# BLOCKS.net
KiCad netlist of a schematic drawn in EAGLE
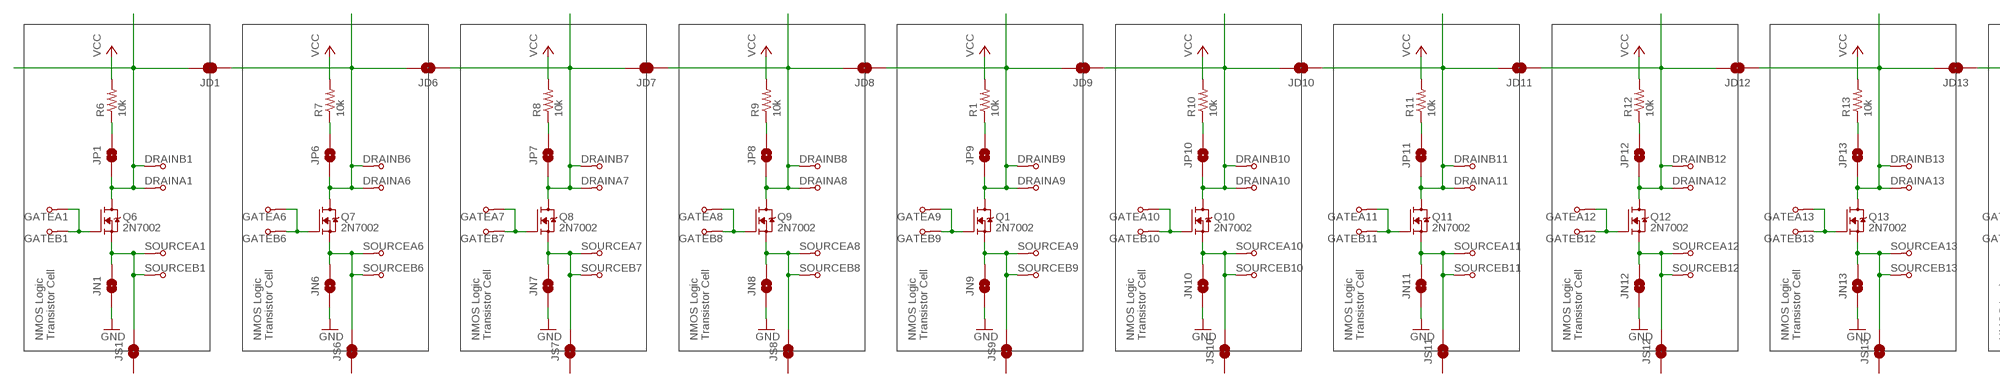
[diagram p0: schematic, sheet 1, part 1 of 2]
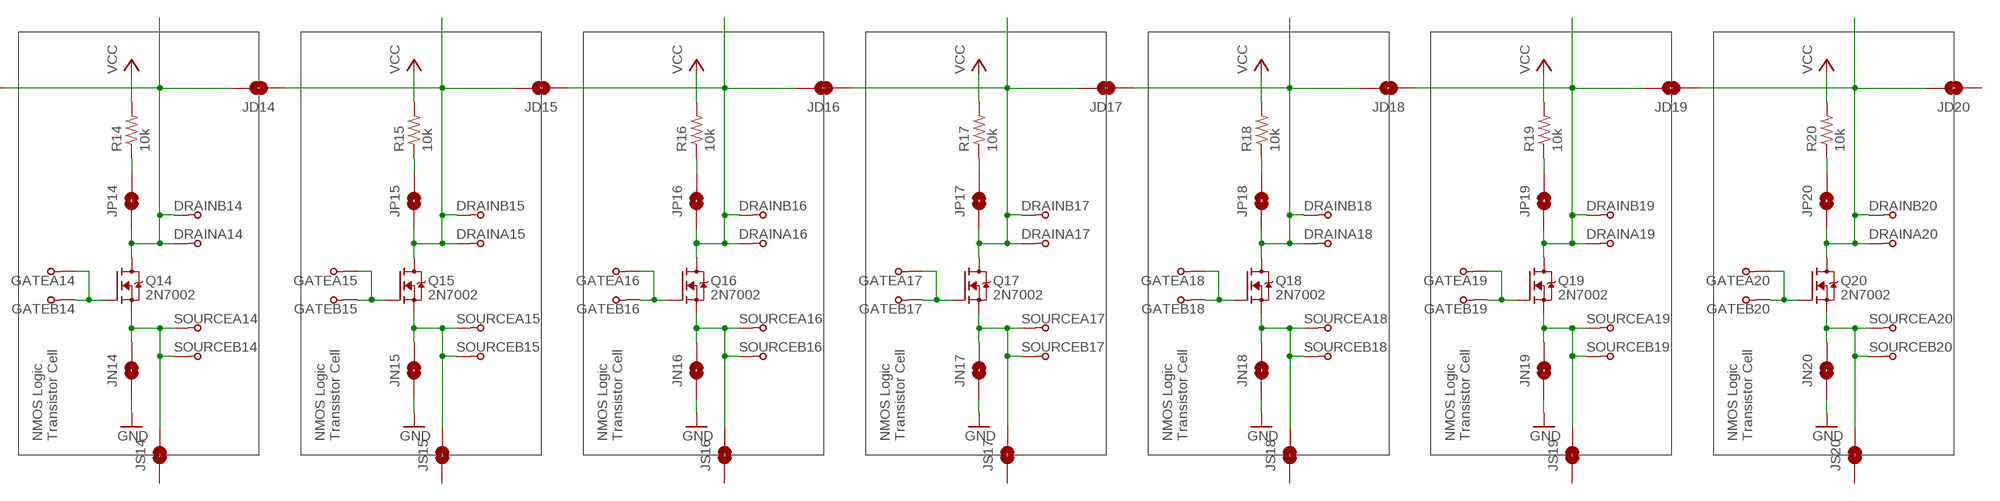
[diagram p1: schematic, sheet 1, part 2 of 2]

(export (version "E")
  (design (tool "Eeschema 10.0.6"))
  (components
    (comp (ref "DRAINA1")
      (value "TPTHT")
      (footprint "eagle-import:PROTOPAD-THT-PAD")
      (libsource (lib "eagle-import") (part "TPTHT"))
    )
    (comp (ref "DRAINA6")
      (value "TPTHT")
      (footprint "eagle-import:PROTOPAD-THT-PAD")
      (libsource (lib "eagle-import") (part "TPTHT"))
    )
    (comp (ref "DRAINA7")
      (value "TPTHT")
      (footprint "eagle-import:PROTOPAD-THT-PAD")
      (libsource (lib "eagle-import") (part "TPTHT"))
    )
    (comp (ref "DRAINA8")
      (value "TPTHT")
      (footprint "eagle-import:PROTOPAD-THT-PAD")
      (libsource (lib "eagle-import") (part "TPTHT"))
    )
    (comp (ref "DRAINA9")
      (value "TPTHT")
      (footprint "eagle-import:PROTOPAD-THT-PAD")
      (libsource (lib "eagle-import") (part "TPTHT"))
    )
    (comp (ref "DRAINA10")
      (value "TPTHT")
      (footprint "eagle-import:PROTOPAD-THT-PAD")
      (libsource (lib "eagle-import") (part "TPTHT"))
    )
    (comp (ref "DRAINA11")
      (value "TPTHT")
      (footprint "eagle-import:PROTOPAD-THT-PAD")
      (libsource (lib "eagle-import") (part "TPTHT"))
    )
    (comp (ref "DRAINA12")
      (value "TPTHT")
      (footprint "eagle-import:PROTOPAD-THT-PAD")
      (libsource (lib "eagle-import") (part "TPTHT"))
    )
    (comp (ref "DRAINA13")
      (value "TPTHT")
      (footprint "eagle-import:PROTOPAD-THT-PAD")
      (libsource (lib "eagle-import") (part "TPTHT"))
    )
    (comp (ref "DRAINA14")
      (value "TPTHT")
      (footprint "eagle-import:PROTOPAD-THT-PAD")
      (libsource (lib "eagle-import") (part "TPTHT"))
    )
    (comp (ref "DRAINA15")
      (value "TPTHT")
      (footprint "eagle-import:PROTOPAD-THT-PAD")
      (libsource (lib "eagle-import") (part "TPTHT"))
    )
    (comp (ref "DRAINA16")
      (value "TPTHT")
      (footprint "eagle-import:PROTOPAD-THT-PAD")
      (libsource (lib "eagle-import") (part "TPTHT"))
    )
    (comp (ref "DRAINA17")
      (value "TPTHT")
      (footprint "eagle-import:PROTOPAD-THT-PAD")
      (libsource (lib "eagle-import") (part "TPTHT"))
    )
    (comp (ref "DRAINA18")
      (value "TPTHT")
      (footprint "eagle-import:PROTOPAD-THT-PAD")
      (libsource (lib "eagle-import") (part "TPTHT"))
    )
    (comp (ref "DRAINA19")
      (value "TPTHT")
      (footprint "eagle-import:PROTOPAD-THT-PAD")
      (libsource (lib "eagle-import") (part "TPTHT"))
    )
    (comp (ref "DRAINA20")
      (value "TPTHT")
      (footprint "eagle-import:PROTOPAD-THT-PAD")
      (libsource (lib "eagle-import") (part "TPTHT"))
    )
    (comp (ref "DRAINB1")
      (value "TPTHT")
      (footprint "eagle-import:PROTOPAD-THT-PAD")
      (libsource (lib "eagle-import") (part "TPTHT"))
    )
    (comp (ref "DRAINB6")
      (value "TPTHT")
      (footprint "eagle-import:PROTOPAD-THT-PAD")
      (libsource (lib "eagle-import") (part "TPTHT"))
    )
    (comp (ref "DRAINB7")
      (value "TPTHT")
      (footprint "eagle-import:PROTOPAD-THT-PAD")
      (libsource (lib "eagle-import") (part "TPTHT"))
    )
    (comp (ref "DRAINB8")
      (value "TPTHT")
      (footprint "eagle-import:PROTOPAD-THT-PAD")
      (libsource (lib "eagle-import") (part "TPTHT"))
    )
    (comp (ref "DRAINB9")
      (value "TPTHT")
      (footprint "eagle-import:PROTOPAD-THT-PAD")
      (libsource (lib "eagle-import") (part "TPTHT"))
    )
    (comp (ref "DRAINB10")
      (value "TPTHT")
      (footprint "eagle-import:PROTOPAD-THT-PAD")
      (libsource (lib "eagle-import") (part "TPTHT"))
    )
    (comp (ref "DRAINB11")
      (value "TPTHT")
      (footprint "eagle-import:PROTOPAD-THT-PAD")
      (libsource (lib "eagle-import") (part "TPTHT"))
    )
    (comp (ref "DRAINB12")
      (value "TPTHT")
      (footprint "eagle-import:PROTOPAD-THT-PAD")
      (libsource (lib "eagle-import") (part "TPTHT"))
    )
    (comp (ref "DRAINB13")
      (value "TPTHT")
      (footprint "eagle-import:PROTOPAD-THT-PAD")
      (libsource (lib "eagle-import") (part "TPTHT"))
    )
    (comp (ref "DRAINB14")
      (value "TPTHT")
      (footprint "eagle-import:PROTOPAD-THT-PAD")
      (libsource (lib "eagle-import") (part "TPTHT"))
    )
    (comp (ref "DRAINB15")
      (value "TPTHT")
      (footprint "eagle-import:PROTOPAD-THT-PAD")
      (libsource (lib "eagle-import") (part "TPTHT"))
    )
    (comp (ref "DRAINB16")
      (value "TPTHT")
      (footprint "eagle-import:PROTOPAD-THT-PAD")
      (libsource (lib "eagle-import") (part "TPTHT"))
    )
    (comp (ref "DRAINB17")
      (value "TPTHT")
      (footprint "eagle-import:PROTOPAD-THT-PAD")
      (libsource (lib "eagle-import") (part "TPTHT"))
    )
    (comp (ref "DRAINB18")
      (value "TPTHT")
      (footprint "eagle-import:PROTOPAD-THT-PAD")
      (libsource (lib "eagle-import") (part "TPTHT"))
    )
    (comp (ref "DRAINB19")
      (value "TPTHT")
      (footprint "eagle-import:PROTOPAD-THT-PAD")
      (libsource (lib "eagle-import") (part "TPTHT"))
    )
    (comp (ref "DRAINB20")
      (value "TPTHT")
      (footprint "eagle-import:PROTOPAD-THT-PAD")
      (libsource (lib "eagle-import") (part "TPTHT"))
    )
    (comp (ref "GATEA1")
      (value "TPTHT")
      (footprint "eagle-import:PROTOPAD-THT-PAD")
      (libsource (lib "eagle-import") (part "TPTHT"))
    )
    (comp (ref "GATEA6")
      (value "TPTHT")
      (footprint "eagle-import:PROTOPAD-THT-PAD")
      (libsource (lib "eagle-import") (part "TPTHT"))
    )
    (comp (ref "GATEA7")
      (value "TPTHT")
      (footprint "eagle-import:PROTOPAD-THT-PAD")
      (libsource (lib "eagle-import") (part "TPTHT"))
    )
    (comp (ref "GATEA8")
      (value "TPTHT")
      (footprint "eagle-import:PROTOPAD-THT-PAD")
      (libsource (lib "eagle-import") (part "TPTHT"))
    )
    (comp (ref "GATEA9")
      (value "TPTHT")
      (footprint "eagle-import:PROTOPAD-THT-PAD")
      (libsource (lib "eagle-import") (part "TPTHT"))
    )
    (comp (ref "GATEA10")
      (value "TPTHT")
      (footprint "eagle-import:PROTOPAD-THT-PAD")
      (libsource (lib "eagle-import") (part "TPTHT"))
    )
    (comp (ref "GATEA11")
      (value "TPTHT")
      (footprint "eagle-import:PROTOPAD-THT-PAD")
      (libsource (lib "eagle-import") (part "TPTHT"))
    )
    (comp (ref "GATEA12")
      (value "TPTHT")
      (footprint "eagle-import:PROTOPAD-THT-PAD")
      (libsource (lib "eagle-import") (part "TPTHT"))
    )
    (comp (ref "GATEA13")
      (value "TPTHT")
      (footprint "eagle-import:PROTOPAD-THT-PAD")
      (libsource (lib "eagle-import") (part "TPTHT"))
    )
    (comp (ref "GATEA14")
      (value "TPTHT")
      (footprint "eagle-import:PROTOPAD-THT-PAD")
      (libsource (lib "eagle-import") (part "TPTHT"))
    )
    (comp (ref "GATEA15")
      (value "TPTHT")
      (footprint "eagle-import:PROTOPAD-THT-PAD")
      (libsource (lib "eagle-import") (part "TPTHT"))
    )
    (comp (ref "GATEA16")
      (value "TPTHT")
      (footprint "eagle-import:PROTOPAD-THT-PAD")
      (libsource (lib "eagle-import") (part "TPTHT"))
    )
    (comp (ref "GATEA17")
      (value "TPTHT")
      (footprint "eagle-import:PROTOPAD-THT-PAD")
      (libsource (lib "eagle-import") (part "TPTHT"))
    )
    (comp (ref "GATEA18")
      (value "TPTHT")
      (footprint "eagle-import:PROTOPAD-THT-PAD")
      (libsource (lib "eagle-import") (part "TPTHT"))
    )
    (comp (ref "GATEA19")
      (value "TPTHT")
      (footprint "eagle-import:PROTOPAD-THT-PAD")
      (libsource (lib "eagle-import") (part "TPTHT"))
    )
    (comp (ref "GATEA20")
      (value "TPTHT")
      (footprint "eagle-import:PROTOPAD-THT-PAD")
      (libsource (lib "eagle-import") (part "TPTHT"))
    )
    (comp (ref "GATEB1")
      (value "TPTHT")
      (footprint "eagle-import:PROTOPAD-THT-PAD")
      (libsource (lib "eagle-import") (part "TPTHT"))
    )
    (comp (ref "GATEB6")
      (value "TPTHT")
      (footprint "eagle-import:PROTOPAD-THT-PAD")
      (libsource (lib "eagle-import") (part "TPTHT"))
    )
    (comp (ref "GATEB7")
      (value "TPTHT")
      (footprint "eagle-import:PROTOPAD-THT-PAD")
      (libsource (lib "eagle-import") (part "TPTHT"))
    )
    (comp (ref "GATEB8")
      (value "TPTHT")
      (footprint "eagle-import:PROTOPAD-THT-PAD")
      (libsource (lib "eagle-import") (part "TPTHT"))
    )
    (comp (ref "GATEB9")
      (value "TPTHT")
      (footprint "eagle-import:PROTOPAD-THT-PAD")
      (libsource (lib "eagle-import") (part "TPTHT"))
    )
    (comp (ref "GATEB10")
      (value "TPTHT")
      (footprint "eagle-import:PROTOPAD-THT-PAD")
      (libsource (lib "eagle-import") (part "TPTHT"))
    )
    (comp (ref "GATEB11")
      (value "TPTHT")
      (footprint "eagle-import:PROTOPAD-THT-PAD")
      (libsource (lib "eagle-import") (part "TPTHT"))
    )
    (comp (ref "GATEB12")
      (value "TPTHT")
      (footprint "eagle-import:PROTOPAD-THT-PAD")
      (libsource (lib "eagle-import") (part "TPTHT"))
    )
    (comp (ref "GATEB13")
      (value "TPTHT")
      (footprint "eagle-import:PROTOPAD-THT-PAD")
      (libsource (lib "eagle-import") (part "TPTHT"))
    )
    (comp (ref "GATEB14")
      (value "TPTHT")
      (footprint "eagle-import:PROTOPAD-THT-PAD")
      (libsource (lib "eagle-import") (part "TPTHT"))
    )
    (comp (ref "GATEB15")
      (value "TPTHT")
      (footprint "eagle-import:PROTOPAD-THT-PAD")
      (libsource (lib "eagle-import") (part "TPTHT"))
    )
    (comp (ref "GATEB16")
      (value "TPTHT")
      (footprint "eagle-import:PROTOPAD-THT-PAD")
      (libsource (lib "eagle-import") (part "TPTHT"))
    )
    (comp (ref "GATEB17")
      (value "TPTHT")
      (footprint "eagle-import:PROTOPAD-THT-PAD")
      (libsource (lib "eagle-import") (part "TPTHT"))
    )
    (comp (ref "GATEB18")
      (value "TPTHT")
      (footprint "eagle-import:PROTOPAD-THT-PAD")
      (libsource (lib "eagle-import") (part "TPTHT"))
    )
    (comp (ref "GATEB19")
      (value "TPTHT")
      (footprint "eagle-import:PROTOPAD-THT-PAD")
      (libsource (lib "eagle-import") (part "TPTHT"))
    )
    (comp (ref "GATEB20")
      (value "TPTHT")
      (footprint "eagle-import:PROTOPAD-THT-PAD")
      (libsource (lib "eagle-import") (part "TPTHT"))
    )
    (comp (ref "JD1")
      (value "SJ_NO_THIN")
      (footprint "eagle-import:SJ_2S-NO-THIN")
      (libsource (lib "eagle-import") (part "SJ_NO_THIN"))
    )
    (comp (ref "JD6")
      (value "SJ_NO_THIN")
      (footprint "eagle-import:SJ_2S-NO-THIN")
      (libsource (lib "eagle-import") (part "SJ_NO_THIN"))
    )
    (comp (ref "JD7")
      (value "SJ_NO_THIN")
      (footprint "eagle-import:SJ_2S-NO-THIN")
      (libsource (lib "eagle-import") (part "SJ_NO_THIN"))
    )
    (comp (ref "JD8")
      (value "SJ_NO_THIN")
      (footprint "eagle-import:SJ_2S-NO-THIN")
      (libsource (lib "eagle-import") (part "SJ_NO_THIN"))
    )
    (comp (ref "JD9")
      (value "SJ_NO_THIN")
      (footprint "eagle-import:SJ_2S-NO-THIN")
      (libsource (lib "eagle-import") (part "SJ_NO_THIN"))
    )
    (comp (ref "JD10")
      (value "SJ_NO_THIN")
      (footprint "eagle-import:SJ_2S-NO-THIN")
      (libsource (lib "eagle-import") (part "SJ_NO_THIN"))
    )
    (comp (ref "JD11")
      (value "SJ_NO_THIN")
      (footprint "eagle-import:SJ_2S-NO-THIN")
      (libsource (lib "eagle-import") (part "SJ_NO_THIN"))
    )
    (comp (ref "JD12")
      (value "SJ_NO_THIN")
      (footprint "eagle-import:SJ_2S-NO-THIN")
      (libsource (lib "eagle-import") (part "SJ_NO_THIN"))
    )
    (comp (ref "JD13")
      (value "SJ_NO_THIN")
      (footprint "eagle-import:SJ_2S-NO-THIN")
      (libsource (lib "eagle-import") (part "SJ_NO_THIN"))
    )
    (comp (ref "JD14")
      (value "SJ_NO_THIN")
      (footprint "eagle-import:SJ_2S-NO-THIN")
      (libsource (lib "eagle-import") (part "SJ_NO_THIN"))
    )
    (comp (ref "JD15")
      (value "SJ_NO_THIN")
      (footprint "eagle-import:SJ_2S-NO-THIN")
      (libsource (lib "eagle-import") (part "SJ_NO_THIN"))
    )
    (comp (ref "JD16")
      (value "SJ_NO_THIN")
      (footprint "eagle-import:SJ_2S-NO-THIN")
      (libsource (lib "eagle-import") (part "SJ_NO_THIN"))
    )
    (comp (ref "JD17")
      (value "SJ_NO_THIN")
      (footprint "eagle-import:SJ_2S-NO-THIN")
      (libsource (lib "eagle-import") (part "SJ_NO_THIN"))
    )
    (comp (ref "JD18")
      (value "SJ_NO_THIN")
      (footprint "eagle-import:SJ_2S-NO-THIN")
      (libsource (lib "eagle-import") (part "SJ_NO_THIN"))
    )
    (comp (ref "JD19")
      (value "SJ_NO_THIN")
      (footprint "eagle-import:SJ_2S-NO-THIN")
      (libsource (lib "eagle-import") (part "SJ_NO_THIN"))
    )
    (comp (ref "JD20")
      (value "SJ_NO_THIN")
      (footprint "eagle-import:SJ_2S-NO-THIN")
      (libsource (lib "eagle-import") (part "SJ_NO_THIN"))
    )
    (comp (ref "JN1")
      (value "SJ_NO_THIN")
      (footprint "eagle-import:SJ_2S-NO-THIN")
      (libsource (lib "eagle-import") (part "SJ_NO_THIN"))
    )
    (comp (ref "JN6")
      (value "SJ_NO_THIN")
      (footprint "eagle-import:SJ_2S-NO-THIN")
      (libsource (lib "eagle-import") (part "SJ_NO_THIN"))
    )
    (comp (ref "JN7")
      (value "SJ_NO_THIN")
      (footprint "eagle-import:SJ_2S-NO-THIN")
      (libsource (lib "eagle-import") (part "SJ_NO_THIN"))
    )
    (comp (ref "JN8")
      (value "SJ_NO_THIN")
      (footprint "eagle-import:SJ_2S-NO-THIN")
      (libsource (lib "eagle-import") (part "SJ_NO_THIN"))
    )
    (comp (ref "JN9")
      (value "SJ_NO_THIN")
      (footprint "eagle-import:SJ_2S-NO-THIN")
      (libsource (lib "eagle-import") (part "SJ_NO_THIN"))
    )
    (comp (ref "JN10")
      (value "SJ_NO_THIN")
      (footprint "eagle-import:SJ_2S-NO-THIN")
      (libsource (lib "eagle-import") (part "SJ_NO_THIN"))
    )
    (comp (ref "JN11")
      (value "SJ_NO_THIN")
      (footprint "eagle-import:SJ_2S-NO-THIN")
      (libsource (lib "eagle-import") (part "SJ_NO_THIN"))
    )
    (comp (ref "JN12")
      (value "SJ_NO_THIN")
      (footprint "eagle-import:SJ_2S-NO-THIN")
      (libsource (lib "eagle-import") (part "SJ_NO_THIN"))
    )
    (comp (ref "JN13")
      (value "SJ_NO_THIN")
      (footprint "eagle-import:SJ_2S-NO-THIN")
      (libsource (lib "eagle-import") (part "SJ_NO_THIN"))
    )
    (comp (ref "JN14")
      (value "SJ_NO_THIN")
      (footprint "eagle-import:SJ_2S-NO-THIN")
      (libsource (lib "eagle-import") (part "SJ_NO_THIN"))
    )
    (comp (ref "JN15")
      (value "SJ_NO_THIN")
      (footprint "eagle-import:SJ_2S-NO-THIN")
      (libsource (lib "eagle-import") (part "SJ_NO_THIN"))
    )
    (comp (ref "JN16")
      (value "SJ_NO_THIN")
      (footprint "eagle-import:SJ_2S-NO-THIN")
      (libsource (lib "eagle-import") (part "SJ_NO_THIN"))
    )
    (comp (ref "JN17")
      (value "SJ_NO_THIN")
      (footprint "eagle-import:SJ_2S-NO-THIN")
      (libsource (lib "eagle-import") (part "SJ_NO_THIN"))
    )
    (comp (ref "JN18")
      (value "SJ_NO_THIN")
      (footprint "eagle-import:SJ_2S-NO-THIN")
      (libsource (lib "eagle-import") (part "SJ_NO_THIN"))
    )
    (comp (ref "JN19")
      (value "SJ_NO_THIN")
      (footprint "eagle-import:SJ_2S-NO-THIN")
      (libsource (lib "eagle-import") (part "SJ_NO_THIN"))
    )
    (comp (ref "JN20")
      (value "SJ_NO_THIN")
      (footprint "eagle-import:SJ_2S-NO-THIN")
      (libsource (lib "eagle-import") (part "SJ_NO_THIN"))
    )
    (comp (ref "JP1")
      (value "SJ_NO_THIN")
      (footprint "eagle-import:SJ_2S-NO-THIN")
      (libsource (lib "eagle-import") (part "SJ_NO_THIN"))
    )
    (comp (ref "JP6")
      (value "SJ_NO_THIN")
      (footprint "eagle-import:SJ_2S-NO-THIN")
      (libsource (lib "eagle-import") (part "SJ_NO_THIN"))
    )
    (comp (ref "JP7")
      (value "SJ_NO_THIN")
      (footprint "eagle-import:SJ_2S-NO-THIN")
      (libsource (lib "eagle-import") (part "SJ_NO_THIN"))
    )
    (comp (ref "JP8")
      (value "SJ_NO_THIN")
      (footprint "eagle-import:SJ_2S-NO-THIN")
      (libsource (lib "eagle-import") (part "SJ_NO_THIN"))
    )
    (comp (ref "JP9")
      (value "SJ_NO_THIN")
      (footprint "eagle-import:SJ_2S-NO-THIN")
      (libsource (lib "eagle-import") (part "SJ_NO_THIN"))
    )
    (comp (ref "JP10")
      (value "SJ_NO_THIN")
      (footprint "eagle-import:SJ_2S-NO-THIN")
      (libsource (lib "eagle-import") (part "SJ_NO_THIN"))
    )
    (comp (ref "JP11")
      (value "SJ_NO_THIN")
      (footprint "eagle-import:SJ_2S-NO-THIN")
      (libsource (lib "eagle-import") (part "SJ_NO_THIN"))
    )
    (comp (ref "JP12")
      (value "SJ_NO_THIN")
      (footprint "eagle-import:SJ_2S-NO-THIN")
      (libsource (lib "eagle-import") (part "SJ_NO_THIN"))
    )
    (comp (ref "JP13")
      (value "SJ_NO_THIN")
      (footprint "eagle-import:SJ_2S-NO-THIN")
      (libsource (lib "eagle-import") (part "SJ_NO_THIN"))
    )
    (comp (ref "JP14")
      (value "SJ_NO_THIN")
      (footprint "eagle-import:SJ_2S-NO-THIN")
      (libsource (lib "eagle-import") (part "SJ_NO_THIN"))
    )
    (comp (ref "JP15")
      (value "SJ_NO_THIN")
      (footprint "eagle-import:SJ_2S-NO-THIN")
      (libsource (lib "eagle-import") (part "SJ_NO_THIN"))
    )
    (comp (ref "JP16")
      (value "SJ_NO_THIN")
      (footprint "eagle-import:SJ_2S-NO-THIN")
      (libsource (lib "eagle-import") (part "SJ_NO_THIN"))
    )
    (comp (ref "JP17")
      (value "SJ_NO_THIN")
      (footprint "eagle-import:SJ_2S-NO-THIN")
      (libsource (lib "eagle-import") (part "SJ_NO_THIN"))
    )
    (comp (ref "JP18")
      (value "SJ_NO_THIN")
      (footprint "eagle-import:SJ_2S-NO-THIN")
      (libsource (lib "eagle-import") (part "SJ_NO_THIN"))
    )
    (comp (ref "JP19")
      (value "SJ_NO_THIN")
      (footprint "eagle-import:SJ_2S-NO-THIN")
      (libsource (lib "eagle-import") (part "SJ_NO_THIN"))
    )
    (comp (ref "JP20")
      (value "SJ_NO_THIN")
      (footprint "eagle-import:SJ_2S-NO-THIN")
      (libsource (lib "eagle-import") (part "SJ_NO_THIN"))
    )
    (comp (ref "JS1")
      (value "SJ_NO_THIN")
      (footprint "eagle-import:SJ_2S-NO-THIN")
      (libsource (lib "eagle-import") (part "SJ_NO_THIN"))
    )
    (comp (ref "JS6")
      (value "SJ_NO_THIN")
      (footprint "eagle-import:SJ_2S-NO-THIN")
      (libsource (lib "eagle-import") (part "SJ_NO_THIN"))
    )
    (comp (ref "JS7")
      (value "SJ_NO_THIN")
      (footprint "eagle-import:SJ_2S-NO-THIN")
      (libsource (lib "eagle-import") (part "SJ_NO_THIN"))
    )
    (comp (ref "JS8")
      (value "SJ_NO_THIN")
      (footprint "eagle-import:SJ_2S-NO-THIN")
      (libsource (lib "eagle-import") (part "SJ_NO_THIN"))
    )
    (comp (ref "JS9")
      (value "SJ_NO_THIN")
      (footprint "eagle-import:SJ_2S-NO-THIN")
      (libsource (lib "eagle-import") (part "SJ_NO_THIN"))
    )
    (comp (ref "JS10")
      (value "SJ_NO_THIN")
      (footprint "eagle-import:SJ_2S-NO-THIN")
      (libsource (lib "eagle-import") (part "SJ_NO_THIN"))
    )
    (comp (ref "JS11")
      (value "SJ_NO_THIN")
      (footprint "eagle-import:SJ_2S-NO-THIN")
      (libsource (lib "eagle-import") (part "SJ_NO_THIN"))
    )
    (comp (ref "JS12")
      (value "SJ_NO_THIN")
      (footprint "eagle-import:SJ_2S-NO-THIN")
      (libsource (lib "eagle-import") (part "SJ_NO_THIN"))
    )
    (comp (ref "JS13")
      (value "SJ_NO_THIN")
      (footprint "eagle-import:SJ_2S-NO-THIN")
      (libsource (lib "eagle-import") (part "SJ_NO_THIN"))
    )
    (comp (ref "JS14")
      (value "SJ_NO_THIN")
      (footprint "eagle-import:SJ_2S-NO-THIN")
      (libsource (lib "eagle-import") (part "SJ_NO_THIN"))
    )
    (comp (ref "JS15")
      (value "SJ_NO_THIN")
      (footprint "eagle-import:SJ_2S-NO-THIN")
      (libsource (lib "eagle-import") (part "SJ_NO_THIN"))
    )
    (comp (ref "JS16")
      (value "SJ_NO_THIN")
      (footprint "eagle-import:SJ_2S-NO-THIN")
      (libsource (lib "eagle-import") (part "SJ_NO_THIN"))
    )
    (comp (ref "JS17")
      (value "SJ_NO_THIN")
      (footprint "eagle-import:SJ_2S-NO-THIN")
      (libsource (lib "eagle-import") (part "SJ_NO_THIN"))
    )
    (comp (ref "JS18")
      (value "SJ_NO_THIN")
      (footprint "eagle-import:SJ_2S-NO-THIN")
      (libsource (lib "eagle-import") (part "SJ_NO_THIN"))
    )
    (comp (ref "JS19")
      (value "SJ_NO_THIN")
      (footprint "eagle-import:SJ_2S-NO-THIN")
      (libsource (lib "eagle-import") (part "SJ_NO_THIN"))
    )
    (comp (ref "JS20")
      (value "SJ_NO_THIN")
      (footprint "eagle-import:SJ_2S-NO-THIN")
      (libsource (lib "eagle-import") (part "SJ_NO_THIN"))
    )
    (comp (ref "Q1")
      (value "2N7002")
      (footprint "eagle-import:SOT23")
      (libsource (lib "eagle-import") (part "2N7002"))
    )
    (comp (ref "Q6")
      (value "2N7002")
      (footprint "eagle-import:SOT23")
      (libsource (lib "eagle-import") (part "2N7002"))
    )
    (comp (ref "Q7")
      (value "2N7002")
      (footprint "eagle-import:SOT23")
      (libsource (lib "eagle-import") (part "2N7002"))
    )
    (comp (ref "Q8")
      (value "2N7002")
      (footprint "eagle-import:SOT23")
      (libsource (lib "eagle-import") (part "2N7002"))
    )
    (comp (ref "Q9")
      (value "2N7002")
      (footprint "eagle-import:SOT23")
      (libsource (lib "eagle-import") (part "2N7002"))
    )
    (comp (ref "Q10")
      (value "2N7002")
      (footprint "eagle-import:SOT23")
      (libsource (lib "eagle-import") (part "2N7002"))
    )
    (comp (ref "Q11")
      (value "2N7002")
      (footprint "eagle-import:SOT23")
      (libsource (lib "eagle-import") (part "2N7002"))
    )
    (comp (ref "Q12")
      (value "2N7002")
      (footprint "eagle-import:SOT23")
      (libsource (lib "eagle-import") (part "2N7002"))
    )
    (comp (ref "Q13")
      (value "2N7002")
      (footprint "eagle-import:SOT23")
      (libsource (lib "eagle-import") (part "2N7002"))
    )
    (comp (ref "Q14")
      (value "2N7002")
      (footprint "eagle-import:SOT23")
      (libsource (lib "eagle-import") (part "2N7002"))
    )
    (comp (ref "Q15")
      (value "2N7002")
      (footprint "eagle-import:SOT23")
      (libsource (lib "eagle-import") (part "2N7002"))
    )
    (comp (ref "Q16")
      (value "2N7002")
      (footprint "eagle-import:SOT23")
      (libsource (lib "eagle-import") (part "2N7002"))
    )
    (comp (ref "Q17")
      (value "2N7002")
      (footprint "eagle-import:SOT23")
      (libsource (lib "eagle-import") (part "2N7002"))
    )
    (comp (ref "Q18")
      (value "2N7002")
      (footprint "eagle-import:SOT23")
      (libsource (lib "eagle-import") (part "2N7002"))
    )
    (comp (ref "Q19")
      (value "2N7002")
      (footprint "eagle-import:SOT23")
      (libsource (lib "eagle-import") (part "2N7002"))
    )
    (comp (ref "Q20")
      (value "2N7002")
      (footprint "eagle-import:SOT23")
      (libsource (lib "eagle-import") (part "2N7002"))
    )
    (comp (ref "R1")
      (value "10k")
      (footprint "eagle-import:R0603")
      (libsource (lib "eagle-import") (part "RES0603"))
    )
    (comp (ref "R6")
      (value "10k")
      (footprint "eagle-import:R0603")
      (libsource (lib "eagle-import") (part "RES0603"))
    )
    (comp (ref "R7")
      (value "10k")
      (footprint "eagle-import:R0603")
      (libsource (lib "eagle-import") (part "RES0603"))
    )
    (comp (ref "R8")
      (value "10k")
      (footprint "eagle-import:R0603")
      (libsource (lib "eagle-import") (part "RES0603"))
    )
    (comp (ref "R9")
      (value "10k")
      (footprint "eagle-import:R0603")
      (libsource (lib "eagle-import") (part "RES0603"))
    )
    (comp (ref "R10")
      (value "10k")
      (footprint "eagle-import:R0603")
      (libsource (lib "eagle-import") (part "RES0603"))
    )
    (comp (ref "R11")
      (value "10k")
      (footprint "eagle-import:R0603")
      (libsource (lib "eagle-import") (part "RES0603"))
    )
    (comp (ref "R12")
      (value "10k")
      (footprint "eagle-import:R0603")
      (libsource (lib "eagle-import") (part "RES0603"))
    )
    (comp (ref "R13")
      (value "10k")
      (footprint "eagle-import:R0603")
      (libsource (lib "eagle-import") (part "RES0603"))
    )
    (comp (ref "R14")
      (value "10k")
      (footprint "eagle-import:R0603")
      (libsource (lib "eagle-import") (part "RES0603"))
    )
    (comp (ref "R15")
      (value "10k")
      (footprint "eagle-import:R0603")
      (libsource (lib "eagle-import") (part "RES0603"))
    )
    (comp (ref "R16")
      (value "10k")
      (footprint "eagle-import:R0603")
      (libsource (lib "eagle-import") (part "RES0603"))
    )
    (comp (ref "R17")
      (value "10k")
      (footprint "eagle-import:R0603")
      (libsource (lib "eagle-import") (part "RES0603"))
    )
    (comp (ref "R18")
      (value "10k")
      (footprint "eagle-import:R0603")
      (libsource (lib "eagle-import") (part "RES0603"))
    )
    (comp (ref "R19")
      (value "10k")
      (footprint "eagle-import:R0603")
      (libsource (lib "eagle-import") (part "RES0603"))
    )
    (comp (ref "R20")
      (value "10k")
      (footprint "eagle-import:R0603")
      (libsource (lib "eagle-import") (part "RES0603"))
    )
    (comp (ref "SOURCEA1")
      (value "TPTHT")
      (footprint "eagle-import:PROTOPAD-THT-PAD")
      (libsource (lib "eagle-import") (part "TPTHT"))
    )
    (comp (ref "SOURCEA6")
      (value "TPTHT")
      (footprint "eagle-import:PROTOPAD-THT-PAD")
      (libsource (lib "eagle-import") (part "TPTHT"))
    )
    (comp (ref "SOURCEA7")
      (value "TPTHT")
      (footprint "eagle-import:PROTOPAD-THT-PAD")
      (libsource (lib "eagle-import") (part "TPTHT"))
    )
    (comp (ref "SOURCEA8")
      (value "TPTHT")
      (footprint "eagle-import:PROTOPAD-THT-PAD")
      (libsource (lib "eagle-import") (part "TPTHT"))
    )
    (comp (ref "SOURCEA9")
      (value "TPTHT")
      (footprint "eagle-import:PROTOPAD-THT-PAD")
      (libsource (lib "eagle-import") (part "TPTHT"))
    )
    (comp (ref "SOURCEA10")
      (value "TPTHT")
      (footprint "eagle-import:PROTOPAD-THT-PAD")
      (libsource (lib "eagle-import") (part "TPTHT"))
    )
    (comp (ref "SOURCEA11")
      (value "TPTHT")
      (footprint "eagle-import:PROTOPAD-THT-PAD")
      (libsource (lib "eagle-import") (part "TPTHT"))
    )
    (comp (ref "SOURCEA12")
      (value "TPTHT")
      (footprint "eagle-import:PROTOPAD-THT-PAD")
      (libsource (lib "eagle-import") (part "TPTHT"))
    )
    (comp (ref "SOURCEA13")
      (value "TPTHT")
      (footprint "eagle-import:PROTOPAD-THT-PAD")
      (libsource (lib "eagle-import") (part "TPTHT"))
    )
    (comp (ref "SOURCEA14")
      (value "TPTHT")
      (footprint "eagle-import:PROTOPAD-THT-PAD")
      (libsource (lib "eagle-import") (part "TPTHT"))
    )
    (comp (ref "SOURCEA15")
      (value "TPTHT")
      (footprint "eagle-import:PROTOPAD-THT-PAD")
      (libsource (lib "eagle-import") (part "TPTHT"))
    )
    (comp (ref "SOURCEA16")
      (value "TPTHT")
      (footprint "eagle-import:PROTOPAD-THT-PAD")
      (libsource (lib "eagle-import") (part "TPTHT"))
    )
    (comp (ref "SOURCEA17")
      (value "TPTHT")
      (footprint "eagle-import:PROTOPAD-THT-PAD")
      (libsource (lib "eagle-import") (part "TPTHT"))
    )
    (comp (ref "SOURCEA18")
      (value "TPTHT")
      (footprint "eagle-import:PROTOPAD-THT-PAD")
      (libsource (lib "eagle-import") (part "TPTHT"))
    )
    (comp (ref "SOURCEA19")
      (value "TPTHT")
      (footprint "eagle-import:PROTOPAD-THT-PAD")
      (libsource (lib "eagle-import") (part "TPTHT"))
    )
    (comp (ref "SOURCEA20")
      (value "TPTHT")
      (footprint "eagle-import:PROTOPAD-THT-PAD")
      (libsource (lib "eagle-import") (part "TPTHT"))
    )
    (comp (ref "SOURCEB1")
      (value "TPTHT")
      (footprint "eagle-import:PROTOPAD-THT-PAD")
      (libsource (lib "eagle-import") (part "TPTHT"))
    )
    (comp (ref "SOURCEB6")
      (value "TPTHT")
      (footprint "eagle-import:PROTOPAD-THT-PAD")
      (libsource (lib "eagle-import") (part "TPTHT"))
    )
    (comp (ref "SOURCEB7")
      (value "TPTHT")
      (footprint "eagle-import:PROTOPAD-THT-PAD")
      (libsource (lib "eagle-import") (part "TPTHT"))
    )
    (comp (ref "SOURCEB8")
      (value "TPTHT")
      (footprint "eagle-import:PROTOPAD-THT-PAD")
      (libsource (lib "eagle-import") (part "TPTHT"))
    )
    (comp (ref "SOURCEB9")
      (value "TPTHT")
      (footprint "eagle-import:PROTOPAD-THT-PAD")
      (libsource (lib "eagle-import") (part "TPTHT"))
    )
    (comp (ref "SOURCEB10")
      (value "TPTHT")
      (footprint "eagle-import:PROTOPAD-THT-PAD")
      (libsource (lib "eagle-import") (part "TPTHT"))
    )
    (comp (ref "SOURCEB11")
      (value "TPTHT")
      (footprint "eagle-import:PROTOPAD-THT-PAD")
      (libsource (lib "eagle-import") (part "TPTHT"))
    )
    (comp (ref "SOURCEB12")
      (value "TPTHT")
      (footprint "eagle-import:PROTOPAD-THT-PAD")
      (libsource (lib "eagle-import") (part "TPTHT"))
    )
    (comp (ref "SOURCEB13")
      (value "TPTHT")
      (footprint "eagle-import:PROTOPAD-THT-PAD")
      (libsource (lib "eagle-import") (part "TPTHT"))
    )
    (comp (ref "SOURCEB14")
      (value "TPTHT")
      (footprint "eagle-import:PROTOPAD-THT-PAD")
      (libsource (lib "eagle-import") (part "TPTHT"))
    )
    (comp (ref "SOURCEB15")
      (value "TPTHT")
      (footprint "eagle-import:PROTOPAD-THT-PAD")
      (libsource (lib "eagle-import") (part "TPTHT"))
    )
    (comp (ref "SOURCEB16")
      (value "TPTHT")
      (footprint "eagle-import:PROTOPAD-THT-PAD")
      (libsource (lib "eagle-import") (part "TPTHT"))
    )
    (comp (ref "SOURCEB17")
      (value "TPTHT")
      (footprint "eagle-import:PROTOPAD-THT-PAD")
      (libsource (lib "eagle-import") (part "TPTHT"))
    )
    (comp (ref "SOURCEB18")
      (value "TPTHT")
      (footprint "eagle-import:PROTOPAD-THT-PAD")
      (libsource (lib "eagle-import") (part "TPTHT"))
    )
    (comp (ref "SOURCEB19")
      (value "TPTHT")
      (footprint "eagle-import:PROTOPAD-THT-PAD")
      (libsource (lib "eagle-import") (part "TPTHT"))
    )
    (comp (ref "SOURCEB20")
      (value "TPTHT")
      (footprint "eagle-import:PROTOPAD-THT-PAD")
      (libsource (lib "eagle-import") (part "TPTHT"))
    )
  )
  (nets
    (net (code "1") (name "GND") (class "Default")
      (node (ref "JN1") (pin "1") (pinfunction "1_1") (pintype "passive"))
      (node (ref "JN10") (pin "1") (pinfunction "1_1") (pintype "passive"))
      (node (ref "JN11") (pin "1") (pinfunction "1_1") (pintype "passive"))
      (node (ref "JN12") (pin "1") (pinfunction "1_1") (pintype "passive"))
      (node (ref "JN13") (pin "1") (pinfunction "1_1") (pintype "passive"))
      (node (ref "JN14") (pin "1") (pinfunction "1_1") (pintype "passive"))
      (node (ref "JN15") (pin "1") (pinfunction "1_1") (pintype "passive"))
      (node (ref "JN16") (pin "1") (pinfunction "1_1") (pintype "passive"))
      (node (ref "JN17") (pin "1") (pinfunction "1_1") (pintype "passive"))
      (node (ref "JN18") (pin "1") (pinfunction "1_1") (pintype "passive"))
      (node (ref "JN19") (pin "1") (pinfunction "1_1") (pintype "passive"))
      (node (ref "JN20") (pin "1") (pinfunction "1_1") (pintype "passive"))
      (node (ref "JN6") (pin "1") (pinfunction "1_1") (pintype "passive"))
      (node (ref "JN7") (pin "1") (pinfunction "1_1") (pintype "passive"))
      (node (ref "JN8") (pin "1") (pinfunction "1_1") (pintype "passive"))
      (node (ref "JN9") (pin "1") (pinfunction "1_1") (pintype "passive"))
    )
    (net (code "2") (name "Net-(DRAINA1-S)") (class "Default")
      (node (ref "DRAINA1") (pin "P1") (pinfunction "S_P1") (pintype "passive"))
      (node (ref "DRAINB1") (pin "P1") (pinfunction "S_P1") (pintype "passive"))
      (node (ref "JD1") (pin "2") (pinfunction "2_2") (pintype "passive"))
      (node (ref "JP1") (pin "1") (pinfunction "1_1") (pintype "passive"))
      (node (ref "Q6") (pin "3") (pinfunction "D_3") (pintype "passive"))
    )
    (net (code "3") (name "Net-(DRAINA6-S)") (class "Default")
      (node (ref "DRAINA6") (pin "P1") (pinfunction "S_P1") (pintype "passive"))
      (node (ref "DRAINB6") (pin "P1") (pinfunction "S_P1") (pintype "passive"))
      (node (ref "JD1") (pin "1") (pinfunction "1_1") (pintype "passive"))
      (node (ref "JD6") (pin "2") (pinfunction "2_2") (pintype "passive"))
      (node (ref "JP6") (pin "1") (pinfunction "1_1") (pintype "passive"))
      (node (ref "Q7") (pin "3") (pinfunction "D_3") (pintype "passive"))
    )
    (net (code "4") (name "Net-(DRAINA7-S)") (class "Default")
      (node (ref "DRAINA7") (pin "P1") (pinfunction "S_P1") (pintype "passive"))
      (node (ref "DRAINB7") (pin "P1") (pinfunction "S_P1") (pintype "passive"))
      (node (ref "JD6") (pin "1") (pinfunction "1_1") (pintype "passive"))
      (node (ref "JD7") (pin "2") (pinfunction "2_2") (pintype "passive"))
      (node (ref "JP7") (pin "1") (pinfunction "1_1") (pintype "passive"))
      (node (ref "Q8") (pin "3") (pinfunction "D_3") (pintype "passive"))
    )
    (net (code "5") (name "Net-(DRAINA8-S)") (class "Default")
      (node (ref "DRAINA8") (pin "P1") (pinfunction "S_P1") (pintype "passive"))
      (node (ref "DRAINB8") (pin "P1") (pinfunction "S_P1") (pintype "passive"))
      (node (ref "JD7") (pin "1") (pinfunction "1_1") (pintype "passive"))
      (node (ref "JD8") (pin "2") (pinfunction "2_2") (pintype "passive"))
      (node (ref "JP8") (pin "1") (pinfunction "1_1") (pintype "passive"))
      (node (ref "Q9") (pin "3") (pinfunction "D_3") (pintype "passive"))
    )
    (net (code "6") (name "Net-(DRAINA9-S)") (class "Default")
      (node (ref "DRAINA9") (pin "P1") (pinfunction "S_P1") (pintype "passive"))
      (node (ref "DRAINB9") (pin "P1") (pinfunction "S_P1") (pintype "passive"))
      (node (ref "JD8") (pin "1") (pinfunction "1_1") (pintype "passive"))
      (node (ref "JD9") (pin "2") (pinfunction "2_2") (pintype "passive"))
      (node (ref "JP9") (pin "1") (pinfunction "1_1") (pintype "passive"))
      (node (ref "Q1") (pin "3") (pinfunction "D_3") (pintype "passive"))
    )
    (net (code "7") (name "Net-(DRAINA10-S)") (class "Default")
      (node (ref "DRAINA10") (pin "P1") (pinfunction "S_P1") (pintype "passive"))
      (node (ref "DRAINB10") (pin "P1") (pinfunction "S_P1") (pintype "passive"))
      (node (ref "JD10") (pin "2") (pinfunction "2_2") (pintype "passive"))
      (node (ref "JD9") (pin "1") (pinfunction "1_1") (pintype "passive"))
      (node (ref "JP10") (pin "1") (pinfunction "1_1") (pintype "passive"))
      (node (ref "Q10") (pin "3") (pinfunction "D_3") (pintype "passive"))
    )
    (net (code "8") (name "Net-(DRAINA11-S)") (class "Default")
      (node (ref "DRAINA11") (pin "P1") (pinfunction "S_P1") (pintype "passive"))
      (node (ref "DRAINB11") (pin "P1") (pinfunction "S_P1") (pintype "passive"))
      (node (ref "JD10") (pin "1") (pinfunction "1_1") (pintype "passive"))
      (node (ref "JD11") (pin "2") (pinfunction "2_2") (pintype "passive"))
      (node (ref "JP11") (pin "1") (pinfunction "1_1") (pintype "passive"))
      (node (ref "Q11") (pin "3") (pinfunction "D_3") (pintype "passive"))
    )
    (net (code "9") (name "Net-(DRAINA12-S)") (class "Default")
      (node (ref "DRAINA12") (pin "P1") (pinfunction "S_P1") (pintype "passive"))
      (node (ref "DRAINB12") (pin "P1") (pinfunction "S_P1") (pintype "passive"))
      (node (ref "JD11") (pin "1") (pinfunction "1_1") (pintype "passive"))
      (node (ref "JD12") (pin "2") (pinfunction "2_2") (pintype "passive"))
      (node (ref "JP12") (pin "1") (pinfunction "1_1") (pintype "passive"))
      (node (ref "Q12") (pin "3") (pinfunction "D_3") (pintype "passive"))
    )
    (net (code "10") (name "Net-(DRAINA13-S)") (class "Default")
      (node (ref "DRAINA13") (pin "P1") (pinfunction "S_P1") (pintype "passive"))
      (node (ref "DRAINB13") (pin "P1") (pinfunction "S_P1") (pintype "passive"))
      (node (ref "JD12") (pin "1") (pinfunction "1_1") (pintype "passive"))
      (node (ref "JD13") (pin "2") (pinfunction "2_2") (pintype "passive"))
      (node (ref "JP13") (pin "1") (pinfunction "1_1") (pintype "passive"))
      (node (ref "Q13") (pin "3") (pinfunction "D_3") (pintype "passive"))
    )
    (net (code "11") (name "Net-(DRAINA14-S)") (class "Default")
      (node (ref "DRAINA14") (pin "P1") (pinfunction "S_P1") (pintype "passive"))
      (node (ref "DRAINB14") (pin "P1") (pinfunction "S_P1") (pintype "passive"))
      (node (ref "JD13") (pin "1") (pinfunction "1_1") (pintype "passive"))
      (node (ref "JD14") (pin "2") (pinfunction "2_2") (pintype "passive"))
      (node (ref "JP14") (pin "1") (pinfunction "1_1") (pintype "passive"))
      (node (ref "Q14") (pin "3") (pinfunction "D_3") (pintype "passive"))
    )
    (net (code "12") (name "Net-(DRAINA15-S)") (class "Default")
      (node (ref "DRAINA15") (pin "P1") (pinfunction "S_P1") (pintype "passive"))
      (node (ref "DRAINB15") (pin "P1") (pinfunction "S_P1") (pintype "passive"))
      (node (ref "JD14") (pin "1") (pinfunction "1_1") (pintype "passive"))
      (node (ref "JD15") (pin "2") (pinfunction "2_2") (pintype "passive"))
      (node (ref "JP15") (pin "1") (pinfunction "1_1") (pintype "passive"))
      (node (ref "Q15") (pin "3") (pinfunction "D_3") (pintype "passive"))
    )
    (net (code "13") (name "Net-(DRAINA16-S)") (class "Default")
      (node (ref "DRAINA16") (pin "P1") (pinfunction "S_P1") (pintype "passive"))
      (node (ref "DRAINB16") (pin "P1") (pinfunction "S_P1") (pintype "passive"))
      (node (ref "JD15") (pin "1") (pinfunction "1_1") (pintype "passive"))
      (node (ref "JD16") (pin "2") (pinfunction "2_2") (pintype "passive"))
      (node (ref "JP16") (pin "1") (pinfunction "1_1") (pintype "passive"))
      (node (ref "Q16") (pin "3") (pinfunction "D_3") (pintype "passive"))
    )
    (net (code "14") (name "Net-(DRAINA17-S)") (class "Default")
      (node (ref "DRAINA17") (pin "P1") (pinfunction "S_P1") (pintype "passive"))
      (node (ref "DRAINB17") (pin "P1") (pinfunction "S_P1") (pintype "passive"))
      (node (ref "JD16") (pin "1") (pinfunction "1_1") (pintype "passive"))
      (node (ref "JD17") (pin "2") (pinfunction "2_2") (pintype "passive"))
      (node (ref "JP17") (pin "1") (pinfunction "1_1") (pintype "passive"))
      (node (ref "Q17") (pin "3") (pinfunction "D_3") (pintype "passive"))
    )
    (net (code "15") (name "Net-(DRAINA18-S)") (class "Default")
      (node (ref "DRAINA18") (pin "P1") (pinfunction "S_P1") (pintype "passive"))
      (node (ref "DRAINB18") (pin "P1") (pinfunction "S_P1") (pintype "passive"))
      (node (ref "JD17") (pin "1") (pinfunction "1_1") (pintype "passive"))
      (node (ref "JD18") (pin "2") (pinfunction "2_2") (pintype "passive"))
      (node (ref "JP18") (pin "1") (pinfunction "1_1") (pintype "passive"))
      (node (ref "Q18") (pin "3") (pinfunction "D_3") (pintype "passive"))
    )
    (net (code "16") (name "Net-(DRAINA19-S)") (class "Default")
      (node (ref "DRAINA19") (pin "P1") (pinfunction "S_P1") (pintype "passive"))
      (node (ref "DRAINB19") (pin "P1") (pinfunction "S_P1") (pintype "passive"))
      (node (ref "JD18") (pin "1") (pinfunction "1_1") (pintype "passive"))
      (node (ref "JD19") (pin "2") (pinfunction "2_2") (pintype "passive"))
      (node (ref "JP19") (pin "1") (pinfunction "1_1") (pintype "passive"))
      (node (ref "Q19") (pin "3") (pinfunction "D_3") (pintype "passive"))
    )
    (net (code "17") (name "Net-(DRAINA20-S)") (class "Default")
      (node (ref "DRAINA20") (pin "P1") (pinfunction "S_P1") (pintype "passive"))
      (node (ref "DRAINB20") (pin "P1") (pinfunction "S_P1") (pintype "passive"))
      (node (ref "JD19") (pin "1") (pinfunction "1_1") (pintype "passive"))
      (node (ref "JD20") (pin "2") (pinfunction "2_2") (pintype "passive"))
      (node (ref "JP20") (pin "1") (pinfunction "1_1") (pintype "passive"))
      (node (ref "Q20") (pin "3") (pinfunction "D_3") (pintype "passive"))
    )
    (net (code "18") (name "Net-(GATEA1-S)") (class "Default")
      (node (ref "GATEA1") (pin "P1") (pinfunction "S_P1") (pintype "passive"))
      (node (ref "GATEB1") (pin "P1") (pinfunction "S_P1") (pintype "passive"))
      (node (ref "Q6") (pin "1") (pinfunction "G_1") (pintype "passive"))
    )
    (net (code "19") (name "Net-(GATEA6-S)") (class "Default")
      (node (ref "GATEA6") (pin "P1") (pinfunction "S_P1") (pintype "passive"))
      (node (ref "GATEB6") (pin "P1") (pinfunction "S_P1") (pintype "passive"))
      (node (ref "Q7") (pin "1") (pinfunction "G_1") (pintype "passive"))
    )
    (net (code "20") (name "Net-(GATEA7-S)") (class "Default")
      (node (ref "GATEA7") (pin "P1") (pinfunction "S_P1") (pintype "passive"))
      (node (ref "GATEB7") (pin "P1") (pinfunction "S_P1") (pintype "passive"))
      (node (ref "Q8") (pin "1") (pinfunction "G_1") (pintype "passive"))
    )
    (net (code "21") (name "Net-(GATEA8-S)") (class "Default")
      (node (ref "GATEA8") (pin "P1") (pinfunction "S_P1") (pintype "passive"))
      (node (ref "GATEB8") (pin "P1") (pinfunction "S_P1") (pintype "passive"))
      (node (ref "Q9") (pin "1") (pinfunction "G_1") (pintype "passive"))
    )
    (net (code "22") (name "Net-(GATEA9-S)") (class "Default")
      (node (ref "GATEA9") (pin "P1") (pinfunction "S_P1") (pintype "passive"))
      (node (ref "GATEB9") (pin "P1") (pinfunction "S_P1") (pintype "passive"))
      (node (ref "Q1") (pin "1") (pinfunction "G_1") (pintype "passive"))
    )
    (net (code "23") (name "Net-(GATEA10-S)") (class "Default")
      (node (ref "GATEA10") (pin "P1") (pinfunction "S_P1") (pintype "passive"))
      (node (ref "GATEB10") (pin "P1") (pinfunction "S_P1") (pintype "passive"))
      (node (ref "Q10") (pin "1") (pinfunction "G_1") (pintype "passive"))
    )
    (net (code "24") (name "Net-(GATEA11-S)") (class "Default")
      (node (ref "GATEA11") (pin "P1") (pinfunction "S_P1") (pintype "passive"))
      (node (ref "GATEB11") (pin "P1") (pinfunction "S_P1") (pintype "passive"))
      (node (ref "Q11") (pin "1") (pinfunction "G_1") (pintype "passive"))
    )
    (net (code "25") (name "Net-(GATEA12-S)") (class "Default")
      (node (ref "GATEA12") (pin "P1") (pinfunction "S_P1") (pintype "passive"))
      (node (ref "GATEB12") (pin "P1") (pinfunction "S_P1") (pintype "passive"))
      (node (ref "Q12") (pin "1") (pinfunction "G_1") (pintype "passive"))
    )
    (net (code "26") (name "Net-(GATEA13-S)") (class "Default")
      (node (ref "GATEA13") (pin "P1") (pinfunction "S_P1") (pintype "passive"))
      (node (ref "GATEB13") (pin "P1") (pinfunction "S_P1") (pintype "passive"))
      (node (ref "Q13") (pin "1") (pinfunction "G_1") (pintype "passive"))
    )
    (net (code "27") (name "Net-(GATEA14-S)") (class "Default")
      (node (ref "GATEA14") (pin "P1") (pinfunction "S_P1") (pintype "passive"))
      (node (ref "GATEB14") (pin "P1") (pinfunction "S_P1") (pintype "passive"))
      (node (ref "Q14") (pin "1") (pinfunction "G_1") (pintype "passive"))
    )
    (net (code "28") (name "Net-(GATEA15-S)") (class "Default")
      (node (ref "GATEA15") (pin "P1") (pinfunction "S_P1") (pintype "passive"))
      (node (ref "GATEB15") (pin "P1") (pinfunction "S_P1") (pintype "passive"))
      (node (ref "Q15") (pin "1") (pinfunction "G_1") (pintype "passive"))
    )
    (net (code "29") (name "Net-(GATEA16-S)") (class "Default")
      (node (ref "GATEA16") (pin "P1") (pinfunction "S_P1") (pintype "passive"))
      (node (ref "GATEB16") (pin "P1") (pinfunction "S_P1") (pintype "passive"))
      (node (ref "Q16") (pin "1") (pinfunction "G_1") (pintype "passive"))
    )
    (net (code "30") (name "Net-(GATEA17-S)") (class "Default")
      (node (ref "GATEA17") (pin "P1") (pinfunction "S_P1") (pintype "passive"))
      (node (ref "GATEB17") (pin "P1") (pinfunction "S_P1") (pintype "passive"))
      (node (ref "Q17") (pin "1") (pinfunction "G_1") (pintype "passive"))
    )
    (net (code "31") (name "Net-(GATEA18-S)") (class "Default")
      (node (ref "GATEA18") (pin "P1") (pinfunction "S_P1") (pintype "passive"))
      (node (ref "GATEB18") (pin "P1") (pinfunction "S_P1") (pintype "passive"))
      (node (ref "Q18") (pin "1") (pinfunction "G_1") (pintype "passive"))
    )
    (net (code "32") (name "Net-(GATEA19-S)") (class "Default")
      (node (ref "GATEA19") (pin "P1") (pinfunction "S_P1") (pintype "passive"))
      (node (ref "GATEB19") (pin "P1") (pinfunction "S_P1") (pintype "passive"))
      (node (ref "Q19") (pin "1") (pinfunction "G_1") (pintype "passive"))
    )
    (net (code "33") (name "Net-(GATEA20-S)") (class "Default")
      (node (ref "GATEA20") (pin "P1") (pinfunction "S_P1") (pintype "passive"))
      (node (ref "GATEB20") (pin "P1") (pinfunction "S_P1") (pintype "passive"))
      (node (ref "Q20") (pin "1") (pinfunction "G_1") (pintype "passive"))
    )
    (net (code "34") (name "Net-(JP1-Pad2)") (class "Default")
      (node (ref "JP1") (pin "2") (pinfunction "2_2") (pintype "passive"))
      (node (ref "R6") (pin "1") (pinfunction "1_1") (pintype "passive"))
    )
    (net (code "35") (name "Net-(JP6-Pad2)") (class "Default")
      (node (ref "JP6") (pin "2") (pinfunction "2_2") (pintype "passive"))
      (node (ref "R7") (pin "1") (pinfunction "1_1") (pintype "passive"))
    )
    (net (code "36") (name "Net-(JP7-Pad2)") (class "Default")
      (node (ref "JP7") (pin "2") (pinfunction "2_2") (pintype "passive"))
      (node (ref "R8") (pin "1") (pinfunction "1_1") (pintype "passive"))
    )
    (net (code "37") (name "Net-(JP8-Pad2)") (class "Default")
      (node (ref "JP8") (pin "2") (pinfunction "2_2") (pintype "passive"))
      (node (ref "R9") (pin "1") (pinfunction "1_1") (pintype "passive"))
    )
    (net (code "38") (name "Net-(JP9-Pad2)") (class "Default")
      (node (ref "JP9") (pin "2") (pinfunction "2_2") (pintype "passive"))
      (node (ref "R1") (pin "1") (pinfunction "1_1") (pintype "passive"))
    )
    (net (code "39") (name "Net-(JP10-Pad2)") (class "Default")
      (node (ref "JP10") (pin "2") (pinfunction "2_2") (pintype "passive"))
      (node (ref "R10") (pin "1") (pinfunction "1_1") (pintype "passive"))
    )
    (net (code "40") (name "Net-(JP11-Pad2)") (class "Default")
      (node (ref "JP11") (pin "2") (pinfunction "2_2") (pintype "passive"))
      (node (ref "R11") (pin "1") (pinfunction "1_1") (pintype "passive"))
    )
    (net (code "41") (name "Net-(JP12-Pad2)") (class "Default")
      (node (ref "JP12") (pin "2") (pinfunction "2_2") (pintype "passive"))
      (node (ref "R12") (pin "1") (pinfunction "1_1") (pintype "passive"))
    )
    (net (code "42") (name "Net-(JP13-Pad2)") (class "Default")
      (node (ref "JP13") (pin "2") (pinfunction "2_2") (pintype "passive"))
      (node (ref "R13") (pin "1") (pinfunction "1_1") (pintype "passive"))
    )
    (net (code "43") (name "Net-(JP14-Pad2)") (class "Default")
      (node (ref "JP14") (pin "2") (pinfunction "2_2") (pintype "passive"))
      (node (ref "R14") (pin "1") (pinfunction "1_1") (pintype "passive"))
    )
    (net (code "44") (name "Net-(JP15-Pad2)") (class "Default")
      (node (ref "JP15") (pin "2") (pinfunction "2_2") (pintype "passive"))
      (node (ref "R15") (pin "1") (pinfunction "1_1") (pintype "passive"))
    )
    (net (code "45") (name "Net-(JP16-Pad2)") (class "Default")
      (node (ref "JP16") (pin "2") (pinfunction "2_2") (pintype "passive"))
      (node (ref "R16") (pin "1") (pinfunction "1_1") (pintype "passive"))
    )
    (net (code "46") (name "Net-(JP17-Pad2)") (class "Default")
      (node (ref "JP17") (pin "2") (pinfunction "2_2") (pintype "passive"))
      (node (ref "R17") (pin "1") (pinfunction "1_1") (pintype "passive"))
    )
    (net (code "47") (name "Net-(JP18-Pad2)") (class "Default")
      (node (ref "JP18") (pin "2") (pinfunction "2_2") (pintype "passive"))
      (node (ref "R18") (pin "1") (pinfunction "1_1") (pintype "passive"))
    )
    (net (code "48") (name "Net-(JP19-Pad2)") (class "Default")
      (node (ref "JP19") (pin "2") (pinfunction "2_2") (pintype "passive"))
      (node (ref "R19") (pin "1") (pinfunction "1_1") (pintype "passive"))
    )
    (net (code "49") (name "Net-(JP20-Pad2)") (class "Default")
      (node (ref "JP20") (pin "2") (pinfunction "2_2") (pintype "passive"))
      (node (ref "R20") (pin "1") (pinfunction "1_1") (pintype "passive"))
    )
    (net (code "50") (name "Net-(Q1-S)") (class "Default")
      (node (ref "JN9") (pin "2") (pinfunction "2_2") (pintype "passive"))
      (node (ref "JS9") (pin "2") (pinfunction "2_2") (pintype "passive"))
      (node (ref "Q1") (pin "2") (pinfunction "S_2") (pintype "passive"))
      (node (ref "SOURCEA9") (pin "P1") (pinfunction "S_P1") (pintype "passive"))
      (node (ref "SOURCEB9") (pin "P1") (pinfunction "S_P1") (pintype "passive"))
    )
    (net (code "51") (name "Net-(Q6-S)") (class "Default")
      (node (ref "JN1") (pin "2") (pinfunction "2_2") (pintype "passive"))
      (node (ref "JS1") (pin "2") (pinfunction "2_2") (pintype "passive"))
      (node (ref "Q6") (pin "2") (pinfunction "S_2") (pintype "passive"))
      (node (ref "SOURCEA1") (pin "P1") (pinfunction "S_P1") (pintype "passive"))
      (node (ref "SOURCEB1") (pin "P1") (pinfunction "S_P1") (pintype "passive"))
    )
    (net (code "52") (name "Net-(Q7-S)") (class "Default")
      (node (ref "JN6") (pin "2") (pinfunction "2_2") (pintype "passive"))
      (node (ref "JS6") (pin "2") (pinfunction "2_2") (pintype "passive"))
      (node (ref "Q7") (pin "2") (pinfunction "S_2") (pintype "passive"))
      (node (ref "SOURCEA6") (pin "P1") (pinfunction "S_P1") (pintype "passive"))
      (node (ref "SOURCEB6") (pin "P1") (pinfunction "S_P1") (pintype "passive"))
    )
    (net (code "53") (name "Net-(Q8-S)") (class "Default")
      (node (ref "JN7") (pin "2") (pinfunction "2_2") (pintype "passive"))
      (node (ref "JS7") (pin "2") (pinfunction "2_2") (pintype "passive"))
      (node (ref "Q8") (pin "2") (pinfunction "S_2") (pintype "passive"))
      (node (ref "SOURCEA7") (pin "P1") (pinfunction "S_P1") (pintype "passive"))
      (node (ref "SOURCEB7") (pin "P1") (pinfunction "S_P1") (pintype "passive"))
    )
    (net (code "54") (name "Net-(Q9-S)") (class "Default")
      (node (ref "JN8") (pin "2") (pinfunction "2_2") (pintype "passive"))
      (node (ref "JS8") (pin "2") (pinfunction "2_2") (pintype "passive"))
      (node (ref "Q9") (pin "2") (pinfunction "S_2") (pintype "passive"))
      (node (ref "SOURCEA8") (pin "P1") (pinfunction "S_P1") (pintype "passive"))
      (node (ref "SOURCEB8") (pin "P1") (pinfunction "S_P1") (pintype "passive"))
    )
    (net (code "55") (name "Net-(Q10-S)") (class "Default")
      (node (ref "JN10") (pin "2") (pinfunction "2_2") (pintype "passive"))
      (node (ref "JS10") (pin "2") (pinfunction "2_2") (pintype "passive"))
      (node (ref "Q10") (pin "2") (pinfunction "S_2") (pintype "passive"))
      (node (ref "SOURCEA10") (pin "P1") (pinfunction "S_P1") (pintype "passive"))
      (node (ref "SOURCEB10") (pin "P1") (pinfunction "S_P1") (pintype "passive"))
    )
    (net (code "56") (name "Net-(Q11-S)") (class "Default")
      (node (ref "JN11") (pin "2") (pinfunction "2_2") (pintype "passive"))
      (node (ref "JS11") (pin "2") (pinfunction "2_2") (pintype "passive"))
      (node (ref "Q11") (pin "2") (pinfunction "S_2") (pintype "passive"))
      (node (ref "SOURCEA11") (pin "P1") (pinfunction "S_P1") (pintype "passive"))
      (node (ref "SOURCEB11") (pin "P1") (pinfunction "S_P1") (pintype "passive"))
    )
    (net (code "57") (name "Net-(Q12-S)") (class "Default")
      (node (ref "JN12") (pin "2") (pinfunction "2_2") (pintype "passive"))
      (node (ref "JS12") (pin "2") (pinfunction "2_2") (pintype "passive"))
      (node (ref "Q12") (pin "2") (pinfunction "S_2") (pintype "passive"))
      (node (ref "SOURCEA12") (pin "P1") (pinfunction "S_P1") (pintype "passive"))
      (node (ref "SOURCEB12") (pin "P1") (pinfunction "S_P1") (pintype "passive"))
    )
    (net (code "58") (name "Net-(Q13-S)") (class "Default")
      (node (ref "JN13") (pin "2") (pinfunction "2_2") (pintype "passive"))
      (node (ref "JS13") (pin "2") (pinfunction "2_2") (pintype "passive"))
      (node (ref "Q13") (pin "2") (pinfunction "S_2") (pintype "passive"))
      (node (ref "SOURCEA13") (pin "P1") (pinfunction "S_P1") (pintype "passive"))
      (node (ref "SOURCEB13") (pin "P1") (pinfunction "S_P1") (pintype "passive"))
    )
    (net (code "59") (name "Net-(Q14-S)") (class "Default")
      (node (ref "JN14") (pin "2") (pinfunction "2_2") (pintype "passive"))
      (node (ref "JS14") (pin "2") (pinfunction "2_2") (pintype "passive"))
      (node (ref "Q14") (pin "2") (pinfunction "S_2") (pintype "passive"))
      (node (ref "SOURCEA14") (pin "P1") (pinfunction "S_P1") (pintype "passive"))
      (node (ref "SOURCEB14") (pin "P1") (pinfunction "S_P1") (pintype "passive"))
    )
    (net (code "60") (name "Net-(Q15-S)") (class "Default")
      (node (ref "JN15") (pin "2") (pinfunction "2_2") (pintype "passive"))
      (node (ref "JS15") (pin "2") (pinfunction "2_2") (pintype "passive"))
      (node (ref "Q15") (pin "2") (pinfunction "S_2") (pintype "passive"))
      (node (ref "SOURCEA15") (pin "P1") (pinfunction "S_P1") (pintype "passive"))
      (node (ref "SOURCEB15") (pin "P1") (pinfunction "S_P1") (pintype "passive"))
    )
    (net (code "61") (name "Net-(Q16-S)") (class "Default")
      (node (ref "JN16") (pin "2") (pinfunction "2_2") (pintype "passive"))
      (node (ref "JS16") (pin "2") (pinfunction "2_2") (pintype "passive"))
      (node (ref "Q16") (pin "2") (pinfunction "S_2") (pintype "passive"))
      (node (ref "SOURCEA16") (pin "P1") (pinfunction "S_P1") (pintype "passive"))
      (node (ref "SOURCEB16") (pin "P1") (pinfunction "S_P1") (pintype "passive"))
    )
    (net (code "62") (name "Net-(Q17-S)") (class "Default")
      (node (ref "JN17") (pin "2") (pinfunction "2_2") (pintype "passive"))
      (node (ref "JS17") (pin "2") (pinfunction "2_2") (pintype "passive"))
      (node (ref "Q17") (pin "2") (pinfunction "S_2") (pintype "passive"))
      (node (ref "SOURCEA17") (pin "P1") (pinfunction "S_P1") (pintype "passive"))
      (node (ref "SOURCEB17") (pin "P1") (pinfunction "S_P1") (pintype "passive"))
    )
    (net (code "63") (name "Net-(Q18-S)") (class "Default")
      (node (ref "JN18") (pin "2") (pinfunction "2_2") (pintype "passive"))
      (node (ref "JS18") (pin "2") (pinfunction "2_2") (pintype "passive"))
      (node (ref "Q18") (pin "2") (pinfunction "S_2") (pintype "passive"))
      (node (ref "SOURCEA18") (pin "P1") (pinfunction "S_P1") (pintype "passive"))
      (node (ref "SOURCEB18") (pin "P1") (pinfunction "S_P1") (pintype "passive"))
    )
    (net (code "64") (name "Net-(Q19-S)") (class "Default")
      (node (ref "JN19") (pin "2") (pinfunction "2_2") (pintype "passive"))
      (node (ref "JS19") (pin "2") (pinfunction "2_2") (pintype "passive"))
      (node (ref "Q19") (pin "2") (pinfunction "S_2") (pintype "passive"))
      (node (ref "SOURCEA19") (pin "P1") (pinfunction "S_P1") (pintype "passive"))
      (node (ref "SOURCEB19") (pin "P1") (pinfunction "S_P1") (pintype "passive"))
    )
    (net (code "65") (name "Net-(Q20-S)") (class "Default")
      (node (ref "JN20") (pin "2") (pinfunction "2_2") (pintype "passive"))
      (node (ref "JS20") (pin "2") (pinfunction "2_2") (pintype "passive"))
      (node (ref "Q20") (pin "2") (pinfunction "S_2") (pintype "passive"))
      (node (ref "SOURCEA20") (pin "P1") (pinfunction "S_P1") (pintype "passive"))
      (node (ref "SOURCEB20") (pin "P1") (pinfunction "S_P1") (pintype "passive"))
    )
    (net (code "66") (name "VCC") (class "Default")
      (node (ref "R1") (pin "2") (pinfunction "2_2") (pintype "passive"))
      (node (ref "R10") (pin "2") (pinfunction "2_2") (pintype "passive"))
      (node (ref "R11") (pin "2") (pinfunction "2_2") (pintype "passive"))
      (node (ref "R12") (pin "2") (pinfunction "2_2") (pintype "passive"))
      (node (ref "R13") (pin "2") (pinfunction "2_2") (pintype "passive"))
      (node (ref "R14") (pin "2") (pinfunction "2_2") (pintype "passive"))
      (node (ref "R15") (pin "2") (pinfunction "2_2") (pintype "passive"))
      (node (ref "R16") (pin "2") (pinfunction "2_2") (pintype "passive"))
      (node (ref "R17") (pin "2") (pinfunction "2_2") (pintype "passive"))
      (node (ref "R18") (pin "2") (pinfunction "2_2") (pintype "passive"))
      (node (ref "R19") (pin "2") (pinfunction "2_2") (pintype "passive"))
      (node (ref "R20") (pin "2") (pinfunction "2_2") (pintype "passive"))
      (node (ref "R6") (pin "2") (pinfunction "2_2") (pintype "passive"))
      (node (ref "R7") (pin "2") (pinfunction "2_2") (pintype "passive"))
      (node (ref "R8") (pin "2") (pinfunction "2_2") (pintype "passive"))
      (node (ref "R9") (pin "2") (pinfunction "2_2") (pintype "passive"))
    )
    (net (code "67") (name "unconnected-(JD20-Pad1)") (class "Default")
      (node (ref "JD20") (pin "1") (pinfunction "1_1") (pintype "passive"))
    )
    (net (code "68") (name "unconnected-(JS1-Pad1)") (class "Default")
      (node (ref "JS1") (pin "1") (pinfunction "1_1") (pintype "passive"))
    )
    (net (code "69") (name "unconnected-(JS6-Pad1)") (class "Default")
      (node (ref "JS6") (pin "1") (pinfunction "1_1") (pintype "passive"))
    )
    (net (code "70") (name "unconnected-(JS7-Pad1)") (class "Default")
      (node (ref "JS7") (pin "1") (pinfunction "1_1") (pintype "passive"))
    )
    (net (code "71") (name "unconnected-(JS8-Pad1)") (class "Default")
      (node (ref "JS8") (pin "1") (pinfunction "1_1") (pintype "passive"))
    )
    (net (code "72") (name "unconnected-(JS9-Pad1)") (class "Default")
      (node (ref "JS9") (pin "1") (pinfunction "1_1") (pintype "passive"))
    )
    (net (code "73") (name "unconnected-(JS10-Pad1)") (class "Default")
      (node (ref "JS10") (pin "1") (pinfunction "1_1") (pintype "passive"))
    )
    (net (code "74") (name "unconnected-(JS11-Pad1)") (class "Default")
      (node (ref "JS11") (pin "1") (pinfunction "1_1") (pintype "passive"))
    )
    (net (code "75") (name "unconnected-(JS12-Pad1)") (class "Default")
      (node (ref "JS12") (pin "1") (pinfunction "1_1") (pintype "passive"))
    )
    (net (code "76") (name "unconnected-(JS13-Pad1)") (class "Default")
      (node (ref "JS13") (pin "1") (pinfunction "1_1") (pintype "passive"))
    )
    (net (code "77") (name "unconnected-(JS14-Pad1)") (class "Default")
      (node (ref "JS14") (pin "1") (pinfunction "1_1") (pintype "passive"))
    )
    (net (code "78") (name "unconnected-(JS15-Pad1)") (class "Default")
      (node (ref "JS15") (pin "1") (pinfunction "1_1") (pintype "passive"))
    )
    (net (code "79") (name "unconnected-(JS16-Pad1)") (class "Default")
      (node (ref "JS16") (pin "1") (pinfunction "1_1") (pintype "passive"))
    )
    (net (code "80") (name "unconnected-(JS17-Pad1)") (class "Default")
      (node (ref "JS17") (pin "1") (pinfunction "1_1") (pintype "passive"))
    )
    (net (code "81") (name "unconnected-(JS18-Pad1)") (class "Default")
      (node (ref "JS18") (pin "1") (pinfunction "1_1") (pintype "passive"))
    )
    (net (code "82") (name "unconnected-(JS19-Pad1)") (class "Default")
      (node (ref "JS19") (pin "1") (pinfunction "1_1") (pintype "passive"))
    )
    (net (code "83") (name "unconnected-(JS20-Pad1)") (class "Default")
      (node (ref "JS20") (pin "1") (pinfunction "1_1") (pintype "passive"))
    )
  )
)
